# Dice_Module.net
KiCad netlist of a schematic drawn in Altium Designer
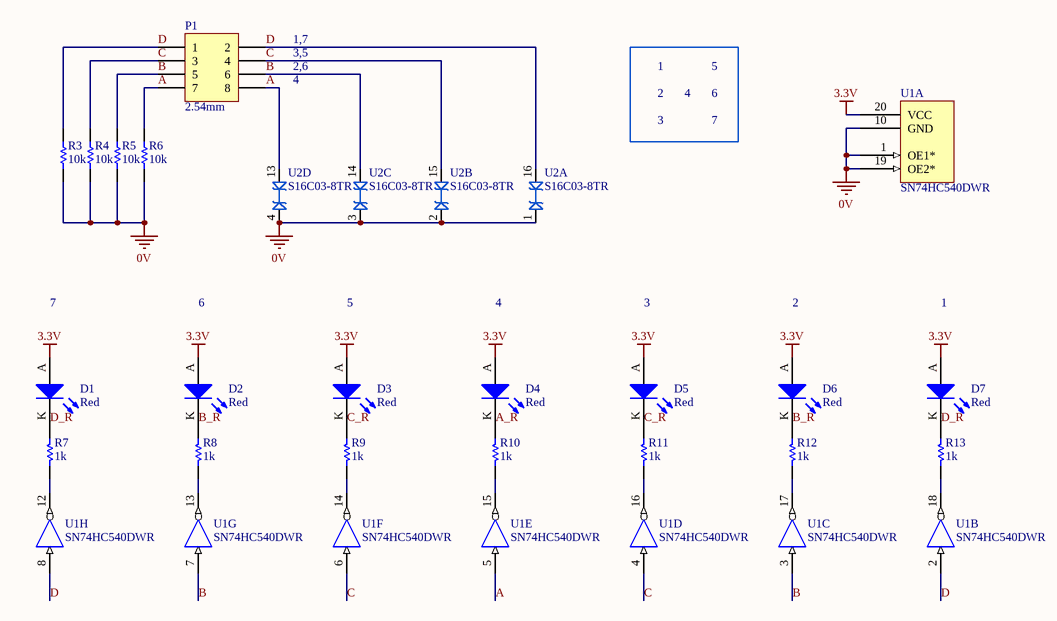
[diagram p0: Dice Module.SchDoc]

(export (version "E")
  (design (tool "Eeschema 10.0.6"))
  (components
    (comp (ref "D1")
      (value "Red")
      (footprint "0805 LED")
      (description "Red LED Indication - Discrete 1.75V 0805 (2012 Metric)")
      (fields (field (name "MANUFACTURER") "ROHM Semiconductor") (field (name "PART NUMBER") "SML-210LTT86"))
      (libsource (lib "ts_19-standard-library") (part "LED"))
    )
    (comp (ref "D2")
      (value "Red")
      (footprint "0805 LED")
      (description "Red LED Indication - Discrete 1.75V 0805 (2012 Metric)")
      (fields (field (name "MANUFACTURER") "ROHM Semiconductor") (field (name "PART NUMBER") "SML-210LTT86"))
      (libsource (lib "ts_19-standard-library") (part "LED"))
    )
    (comp (ref "D3")
      (value "Red")
      (footprint "0805 LED")
      (description "Red LED Indication - Discrete 1.75V 0805 (2012 Metric)")
      (fields (field (name "MANUFACTURER") "ROHM Semiconductor") (field (name "PART NUMBER") "SML-210LTT86"))
      (libsource (lib "ts_19-standard-library") (part "LED"))
    )
    (comp (ref "D4")
      (value "Red")
      (footprint "0805 LED")
      (description "Red LED Indication - Discrete 1.75V 0805 (2012 Metric)")
      (fields (field (name "MANUFACTURER") "ROHM Semiconductor") (field (name "PART NUMBER") "SML-210LTT86"))
      (libsource (lib "ts_19-standard-library") (part "LED"))
    )
    (comp (ref "D5")
      (value "Red")
      (footprint "0805 LED")
      (description "Red LED Indication - Discrete 1.75V 0805 (2012 Metric)")
      (fields (field (name "MANUFACTURER") "ROHM Semiconductor") (field (name "PART NUMBER") "SML-210LTT86"))
      (libsource (lib "ts_19-standard-library") (part "LED"))
    )
    (comp (ref "D6")
      (value "Red")
      (footprint "0805 LED")
      (description "Red LED Indication - Discrete 1.75V 0805 (2012 Metric)")
      (fields (field (name "MANUFACTURER") "ROHM Semiconductor") (field (name "PART NUMBER") "SML-210LTT86"))
      (libsource (lib "ts_19-standard-library") (part "LED"))
    )
    (comp (ref "D7")
      (value "Red")
      (footprint "0805 LED")
      (description "Red LED Indication - Discrete 1.75V 0805 (2012 Metric)")
      (fields (field (name "MANUFACTURER") "ROHM Semiconductor") (field (name "PART NUMBER") "SML-210LTT86"))
      (libsource (lib "ts_19-standard-library") (part "LED"))
    )
    (comp (ref "P1")
      (value "2.54mm")
      (footprint "Header 2x4")
      (fields (field (name "PART NUMBER") "Header 2x4") (field (name "CONTACT") "NA"))
      (libsource (lib "ts_19-standard-connectors-IED") (part "Header 2x4"))
    )
    (comp (ref "R3")
      (value "10k")
      (footprint "0805")
      (fields
        (field (name "MANUFACTURER") "YAGEO")
        (field (name "PART NUMBER") "RC0805FR0710KL")
        (field (name "TOLERANCE") "0.01")
      )
      (libsource (lib "ts_19-standard-library-IED") (part "Resistor"))
    )
    (comp (ref "R4")
      (value "10k")
      (footprint "0805")
      (fields
        (field (name "MANUFACTURER") "YAGEO")
        (field (name "PART NUMBER") "RC0805FR0710KL")
        (field (name "TOLERANCE") "0.01")
      )
      (libsource (lib "ts_19-standard-library-IED") (part "Resistor"))
    )
    (comp (ref "R5")
      (value "10k")
      (footprint "0805")
      (fields
        (field (name "MANUFACTURER") "YAGEO")
        (field (name "PART NUMBER") "RC0805FR0710KL")
        (field (name "TOLERANCE") "0.01")
      )
      (libsource (lib "ts_19-standard-library-IED") (part "Resistor"))
    )
    (comp (ref "R6")
      (value "10k")
      (footprint "0805")
      (fields
        (field (name "MANUFACTURER") "YAGEO")
        (field (name "PART NUMBER") "RC0805FR0710KL")
        (field (name "TOLERANCE") "0.01")
      )
      (libsource (lib "ts_19-standard-library-IED") (part "Resistor"))
    )
    (comp (ref "R7")
      (value "1k")
      (footprint "0805")
      (fields
        (field (name "MANUFACTURER") "YAGEO")
        (field (name "PART NUMBER") "RC0805FR071KL")
        (field (name "TOLERANCE") "0.01")
      )
      (libsource (lib "ts_19-standard-library-IED") (part "Resistor"))
    )
    (comp (ref "R8")
      (value "1k")
      (footprint "0805")
      (fields
        (field (name "MANUFACTURER") "YAGEO")
        (field (name "PART NUMBER") "RC0805FR071KL")
        (field (name "TOLERANCE") "0.01")
      )
      (libsource (lib "ts_19-standard-library-IED") (part "Resistor"))
    )
    (comp (ref "R9")
      (value "1k")
      (footprint "0805")
      (fields
        (field (name "MANUFACTURER") "YAGEO")
        (field (name "PART NUMBER") "RC0805FR071KL")
        (field (name "TOLERANCE") "0.01")
      )
      (libsource (lib "ts_19-standard-library-IED") (part "Resistor"))
    )
    (comp (ref "R10")
      (value "1k")
      (footprint "0805")
      (fields
        (field (name "MANUFACTURER") "YAGEO")
        (field (name "PART NUMBER") "RC0805FR071KL")
        (field (name "TOLERANCE") "0.01")
      )
      (libsource (lib "ts_19-standard-library-IED") (part "Resistor"))
    )
    (comp (ref "R11")
      (value "1k")
      (footprint "0805")
      (fields
        (field (name "MANUFACTURER") "YAGEO")
        (field (name "PART NUMBER") "RC0805FR071KL")
        (field (name "TOLERANCE") "0.01")
      )
      (libsource (lib "ts_19-standard-library-IED") (part "Resistor"))
    )
    (comp (ref "R12")
      (value "1k")
      (footprint "0805")
      (fields
        (field (name "MANUFACTURER") "YAGEO")
        (field (name "PART NUMBER") "RC0805FR071KL")
        (field (name "TOLERANCE") "0.01")
      )
      (libsource (lib "ts_19-standard-library-IED") (part "Resistor"))
    )
    (comp (ref "R13")
      (value "1k")
      (footprint "0805")
      (fields
        (field (name "MANUFACTURER") "YAGEO")
        (field (name "PART NUMBER") "RC0805FR071KL")
        (field (name "TOLERANCE") "0.01")
      )
      (libsource (lib "ts_19-standard-library-IED") (part "Resistor"))
    )
    (comp (ref "U1")
      (value "SN74HC540DWR")
      (footprint "TI 20-SOIC")
      (description "IC BUFFER INVERT 6V 20SOIC")
      (fields
        (field (name "MANUFACTURER") "Texas Instruments")
        (field (name "DIGIKEY PART NUMBER") "296-8333-1-ND")
      )
      (libsource (lib "ts_19-standard-library") (part "SN74HC540DWR"))
    )
    (comp (ref "U2")
      (value "S16C03-8TR")
      (footprint "SMC 16-SOIC")
      (description "PD 300W VWM 3.3VCJ 425PFPACKAGE")
      (fields (field (name "MANUFACTURER") "SMC Diode") (field (name "DIGIKEY PART NUMBER") "1655-2152-2-ND"))
      (libsource (lib "ts_19-standard-library-IED") (part "S16C03-8TR"))
    )
  )
  (nets
    (net (code "1") (name "/A") (class "Default")
      (node (ref "P1") (pin "7") (pinfunction "7_7") (pintype "passive"))
      (node (ref "P1") (pin "8") (pinfunction "8_8") (pintype "passive"))
      (node (ref "R6") (pin "2") (pinfunction "2_2") (pintype "passive"))
      (node (ref "U1") (pin "5") (pinfunction "A4_5") (pintype "input"))
      (node (ref "U2") (pin "13") (pinfunction "A_13") (pintype "passive"))
    )
    (net (code "2") (name "/A_R") (class "Default")
      (node (ref "D4") (pin "K") (pinfunction "K_K") (pintype "passive"))
      (node (ref "R10") (pin "1") (pinfunction "1_1") (pintype "passive"))
    )
    (net (code "3") (name "/B") (class "Default")
      (node (ref "P1") (pin "5") (pinfunction "5_5") (pintype "passive"))
      (node (ref "P1") (pin "6") (pinfunction "6_6") (pintype "passive"))
      (node (ref "R5") (pin "2") (pinfunction "2_2") (pintype "passive"))
      (node (ref "U1") (pin "3") (pinfunction "A2_3") (pintype "input"))
      (node (ref "U1") (pin "7") (pinfunction "A6_7") (pintype "input"))
      (node (ref "U2") (pin "14") (pinfunction "A_14") (pintype "passive"))
    )
    (net (code "4") (name "/B_R") (class "Default")
      (node (ref "D2") (pin "K") (pinfunction "K_K") (pintype "passive"))
      (node (ref "D6") (pin "K") (pinfunction "K_K") (pintype "passive"))
      (node (ref "R12") (pin "1") (pinfunction "1_1") (pintype "passive"))
      (node (ref "R8") (pin "1") (pinfunction "1_1") (pintype "passive"))
    )
    (net (code "5") (name "/C") (class "Default")
      (node (ref "P1") (pin "3") (pinfunction "3_3") (pintype "passive"))
      (node (ref "P1") (pin "4") (pinfunction "4_4") (pintype "passive"))
      (node (ref "R4") (pin "2") (pinfunction "2_2") (pintype "passive"))
      (node (ref "U1") (pin "4") (pinfunction "A3_4") (pintype "input"))
      (node (ref "U1") (pin "6") (pinfunction "A5_6") (pintype "input"))
      (node (ref "U2") (pin "15") (pinfunction "A_15") (pintype "passive"))
    )
    (net (code "6") (name "/C_R") (class "Default")
      (node (ref "D3") (pin "K") (pinfunction "K_K") (pintype "passive"))
      (node (ref "D5") (pin "K") (pinfunction "K_K") (pintype "passive"))
      (node (ref "R11") (pin "1") (pinfunction "1_1") (pintype "passive"))
      (node (ref "R9") (pin "1") (pinfunction "1_1") (pintype "passive"))
    )
    (net (code "7") (name "/D") (class "Default")
      (node (ref "P1") (pin "1") (pinfunction "1_1") (pintype "passive"))
      (node (ref "P1") (pin "2") (pinfunction "2_2") (pintype "passive"))
      (node (ref "R3") (pin "2") (pinfunction "2_2") (pintype "passive"))
      (node (ref "U1") (pin "2") (pinfunction "A1_2") (pintype "input"))
      (node (ref "U1") (pin "8") (pinfunction "A7_8") (pintype "input"))
      (node (ref "U2") (pin "16") (pinfunction "A_16") (pintype "passive"))
    )
    (net (code "8") (name "/D_R") (class "Default")
      (node (ref "D1") (pin "K") (pinfunction "K_K") (pintype "passive"))
      (node (ref "D7") (pin "K") (pinfunction "K_K") (pintype "passive"))
      (node (ref "R13") (pin "1") (pinfunction "1_1") (pintype "passive"))
      (node (ref "R7") (pin "1") (pinfunction "1_1") (pintype "passive"))
    )
    (net (code "9") (name "0V") (class "Default")
      (node (ref "R3") (pin "1") (pinfunction "1_1") (pintype "passive"))
      (node (ref "R4") (pin "1") (pinfunction "1_1") (pintype "passive"))
      (node (ref "R5") (pin "1") (pinfunction "1_1") (pintype "passive"))
      (node (ref "R6") (pin "1") (pinfunction "1_1") (pintype "passive"))
      (node (ref "U1") (pin "1") (pinfunction "OE1*_1") (pintype "input"))
      (node (ref "U1") (pin "10") (pinfunction "GND_10") (pintype "power_in"))
      (node (ref "U1") (pin "19") (pinfunction "OE2*_19") (pintype "input"))
      (node (ref "U2") (pin "1") (pinfunction "A_1") (pintype "passive"))
      (node (ref "U2") (pin "2") (pinfunction "A_2") (pintype "passive"))
      (node (ref "U2") (pin "3") (pinfunction "A_3") (pintype "passive"))
      (node (ref "U2") (pin "4") (pinfunction "A_4") (pintype "passive"))
    )
    (net (code "10") (name "3.3V") (class "Default")
      (node (ref "D1") (pin "A") (pinfunction "A_A") (pintype "passive"))
      (node (ref "D2") (pin "A") (pinfunction "A_A") (pintype "passive"))
      (node (ref "D3") (pin "A") (pinfunction "A_A") (pintype "passive"))
      (node (ref "D4") (pin "A") (pinfunction "A_A") (pintype "passive"))
      (node (ref "D5") (pin "A") (pinfunction "A_A") (pintype "passive"))
      (node (ref "D6") (pin "A") (pinfunction "A_A") (pintype "passive"))
      (node (ref "D7") (pin "A") (pinfunction "A_A") (pintype "passive"))
      (node (ref "U1") (pin "20") (pinfunction "VCC_20") (pintype "power_in"))
    )
    (net (code "11") (name "Net-(U1B-Y1)") (class "Default")
      (node (ref "R13") (pin "2") (pinfunction "2_2") (pintype "passive"))
      (node (ref "U1") (pin "18") (pinfunction "Y1_18") (pintype "output"))
    )
    (net (code "12") (name "Net-(U1C-Y2)") (class "Default")
      (node (ref "R12") (pin "2") (pinfunction "2_2") (pintype "passive"))
      (node (ref "U1") (pin "17") (pinfunction "Y2_17") (pintype "output"))
    )
    (net (code "13") (name "Net-(U1D-Y3)") (class "Default")
      (node (ref "R11") (pin "2") (pinfunction "2_2") (pintype "passive"))
      (node (ref "U1") (pin "16") (pinfunction "Y3_16") (pintype "output"))
    )
    (net (code "14") (name "Net-(U1E-Y5)") (class "Default")
      (node (ref "R10") (pin "2") (pinfunction "2_2") (pintype "passive"))
      (node (ref "U1") (pin "15") (pinfunction "Y5_15") (pintype "output"))
    )
    (net (code "15") (name "Net-(U1F-Y5)") (class "Default")
      (node (ref "R9") (pin "2") (pinfunction "2_2") (pintype "passive"))
      (node (ref "U1") (pin "14") (pinfunction "Y5_14") (pintype "output"))
    )
    (net (code "16") (name "Net-(U1G-Y6)") (class "Default")
      (node (ref "R8") (pin "2") (pinfunction "2_2") (pintype "passive"))
      (node (ref "U1") (pin "13") (pinfunction "Y6_13") (pintype "output"))
    )
    (net (code "17") (name "Net-(U1H-Y7)") (class "Default")
      (node (ref "R7") (pin "2") (pinfunction "2_2") (pintype "passive"))
      (node (ref "U1") (pin "12") (pinfunction "Y7_12") (pintype "output"))
    )
  )
)
